# Mako_DSP_Memory_R2_0.net
KiCad netlist of a schematic drawn in Altium Designer
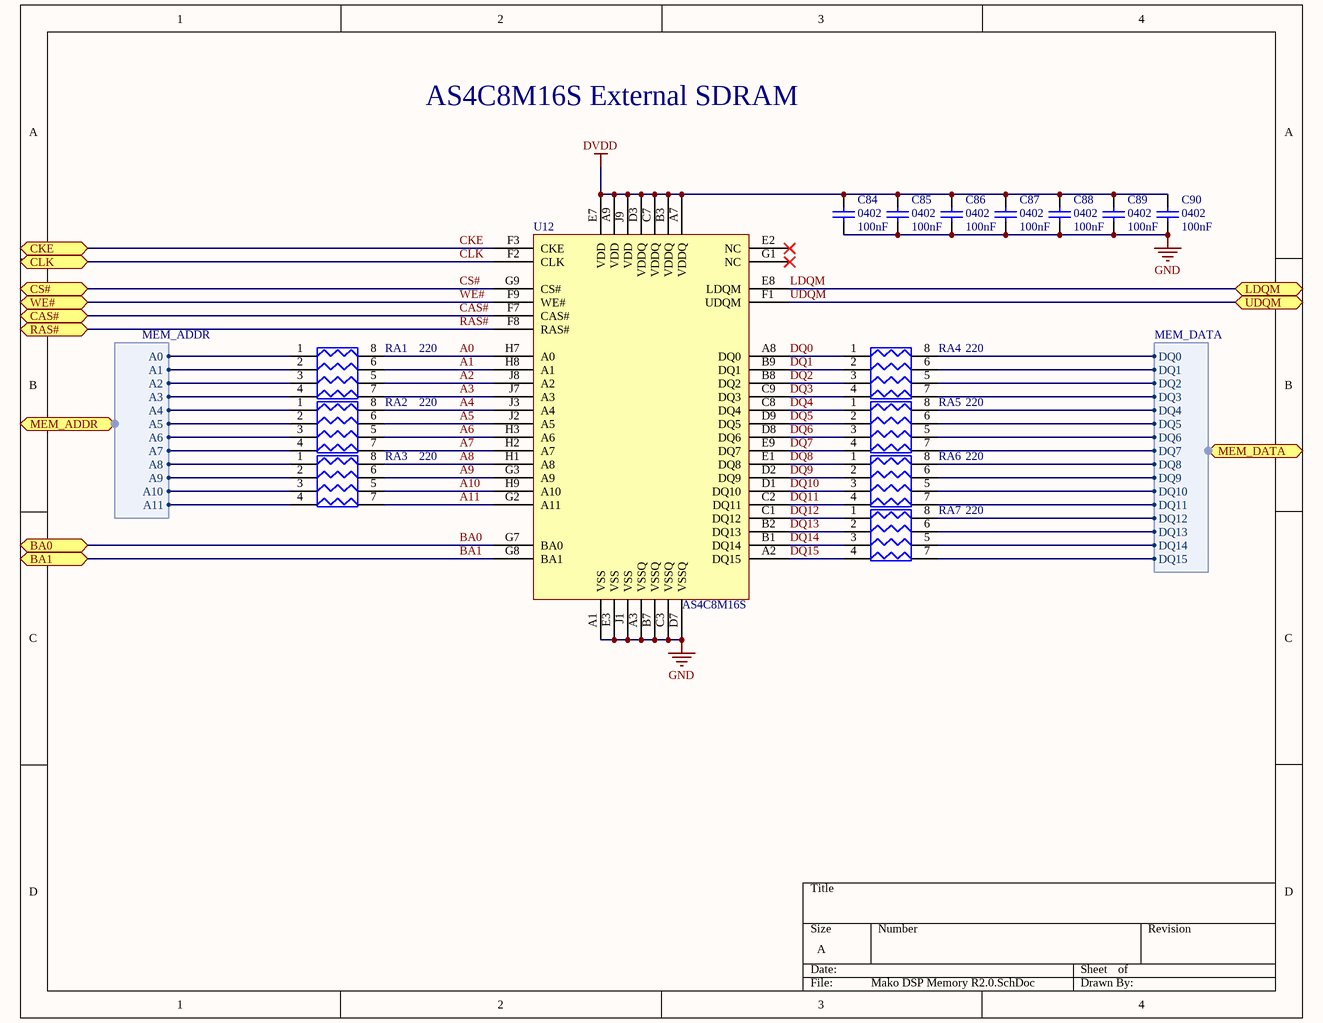
[diagram p0: Mako DSP Memory R2.0.SchDoc]

(export (version "E")
  (design (tool "Eeschema 10.0.6"))
  (components
    (comp (ref "C84")
      (value "0402")
      (footprint "0402")
      (description "Capacitor (Semiconductor SIM Model)")
      (fields (field (name "ALTIUM_VALUE") "100nF") (field (name "PUBLISHER") "Altium Limited"))
      (libsource (lib "Miscellaneous Devices") (part "Cap Semi"))
    )
    (comp (ref "C85")
      (value "0402")
      (footprint "0402")
      (description "Capacitor (Semiconductor SIM Model)")
      (fields (field (name "ALTIUM_VALUE") "100nF") (field (name "PUBLISHER") "Altium Limited"))
      (libsource (lib "Miscellaneous Devices") (part "Cap Semi"))
    )
    (comp (ref "C86")
      (value "0402")
      (footprint "0402")
      (description "Capacitor (Semiconductor SIM Model)")
      (fields (field (name "ALTIUM_VALUE") "100nF") (field (name "PUBLISHER") "Altium Limited"))
      (libsource (lib "Miscellaneous Devices") (part "Cap Semi"))
    )
    (comp (ref "C87")
      (value "0402")
      (footprint "0402")
      (description "Capacitor (Semiconductor SIM Model)")
      (fields (field (name "ALTIUM_VALUE") "100nF") (field (name "PUBLISHER") "Altium Limited"))
      (libsource (lib "Miscellaneous Devices") (part "Cap Semi"))
    )
    (comp (ref "C88")
      (value "0402")
      (footprint "0402")
      (description "Capacitor (Semiconductor SIM Model)")
      (fields (field (name "ALTIUM_VALUE") "100nF") (field (name "PUBLISHER") "Altium Limited"))
      (libsource (lib "Miscellaneous Devices") (part "Cap Semi"))
    )
    (comp (ref "C89")
      (value "0402")
      (footprint "0402")
      (description "Capacitor (Semiconductor SIM Model)")
      (fields (field (name "ALTIUM_VALUE") "100nF") (field (name "PUBLISHER") "Altium Limited"))
      (libsource (lib "Miscellaneous Devices") (part "Cap Semi"))
    )
    (comp (ref "C90")
      (value "0402")
      (footprint "0402")
      (description "Capacitor (Semiconductor SIM Model)")
      (fields (field (name "ALTIUM_VALUE") "100nF") (field (name "PUBLISHER") "Altium Limited"))
      (libsource (lib "Miscellaneous Devices") (part "Cap Semi"))
    )
    (comp (ref "RA1")
      (value "220")
      (footprint "742C083")
      (description "Resistor array")
      (fields (field (name "Comment") "RESISTOR ARRAY"))
      (libsource (lib "Mako DSP Schematic Library") (part "RESISTOR ARRAY"))
    )
    (comp (ref "RA2")
      (value "220")
      (footprint "742C083")
      (description "Resistor array")
      (fields (field (name "Comment") "RESISTOR ARRAY"))
      (libsource (lib "Mako DSP Schematic Library") (part "RESISTOR ARRAY"))
    )
    (comp (ref "RA3")
      (value "220")
      (footprint "742C083")
      (description "Resistor array")
      (fields (field (name "Comment") "RESISTOR ARRAY"))
      (libsource (lib "Mako DSP Schematic Library") (part "RESISTOR ARRAY"))
    )
    (comp (ref "RA4")
      (value "220")
      (footprint "742C083")
      (description "Resistor array")
      (fields (field (name "Comment") "RESISTOR ARRAY"))
      (libsource (lib "Mako DSP Schematic Library") (part "RESISTOR ARRAY"))
    )
    (comp (ref "RA5")
      (value "220")
      (footprint "742C083")
      (description "Resistor array")
      (fields (field (name "Comment") "RESISTOR ARRAY"))
      (libsource (lib "Mako DSP Schematic Library") (part "RESISTOR ARRAY"))
    )
    (comp (ref "RA6")
      (value "220")
      (footprint "742C083")
      (description "Resistor array")
      (fields (field (name "Comment") "RESISTOR ARRAY"))
      (libsource (lib "Mako DSP Schematic Library") (part "RESISTOR ARRAY"))
    )
    (comp (ref "RA7")
      (value "220")
      (footprint "742C083")
      (description "Resistor array")
      (fields (field (name "Comment") "RESISTOR ARRAY"))
      (libsource (lib "Mako DSP Schematic Library") (part "RESISTOR ARRAY"))
    )
    (comp (ref "U12")
      (value "AS4C8M16S")
      (footprint "AS4C8M16S")
      (libsource (lib "Mako DSP Schematic Library") (part "AS4C8M16S"))
    )
  )
  (nets
    (net (code "3") (name "/A0") (class "Default")
      (node (ref "RA1") (pin "8") (pinfunction "8_8") (pintype "passive"))
      (node (ref "U12") (pin "H7") (pinfunction "A0_H7") (pintype "passive"))
    )
    (net (code "4") (name "/A1") (class "Default")
      (node (ref "RA1") (pin "6") (pinfunction "6_6") (pintype "passive"))
      (node (ref "U12") (pin "H8") (pinfunction "A1_H8") (pintype "passive"))
    )
    (net (code "5") (name "/A2") (class "Default")
      (node (ref "RA1") (pin "5") (pinfunction "5_5") (pintype "passive"))
      (node (ref "U12") (pin "J8") (pinfunction "A2_J8") (pintype "passive"))
    )
    (net (code "6") (name "/A3") (class "Default")
      (node (ref "RA1") (pin "7") (pinfunction "7_7") (pintype "passive"))
      (node (ref "U12") (pin "J7") (pinfunction "A3_J7") (pintype "passive"))
    )
    (net (code "7") (name "/A4") (class "Default")
      (node (ref "RA2") (pin "8") (pinfunction "8_8") (pintype "passive"))
      (node (ref "U12") (pin "J3") (pinfunction "A4_J3") (pintype "passive"))
    )
    (net (code "8") (name "/A5") (class "Default")
      (node (ref "RA2") (pin "6") (pinfunction "6_6") (pintype "passive"))
      (node (ref "U12") (pin "J2") (pinfunction "A5_J2") (pintype "passive"))
    )
    (net (code "9") (name "/A6") (class "Default")
      (node (ref "RA2") (pin "5") (pinfunction "5_5") (pintype "passive"))
      (node (ref "U12") (pin "H3") (pinfunction "A6_H3") (pintype "passive"))
    )
    (net (code "10") (name "/A7") (class "Default")
      (node (ref "RA2") (pin "7") (pinfunction "7_7") (pintype "passive"))
      (node (ref "U12") (pin "H2") (pinfunction "A7_H2") (pintype "passive"))
    )
    (net (code "11") (name "/A8") (class "Default")
      (node (ref "RA3") (pin "8") (pinfunction "8_8") (pintype "passive"))
      (node (ref "U12") (pin "H1") (pinfunction "A8_H1") (pintype "passive"))
    )
    (net (code "12") (name "/A9") (class "Default")
      (node (ref "RA3") (pin "6") (pinfunction "6_6") (pintype "passive"))
      (node (ref "U12") (pin "G3") (pinfunction "A9_G3") (pintype "passive"))
    )
    (net (code "13") (name "/A10") (class "Default")
      (node (ref "RA3") (pin "5") (pinfunction "5_5") (pintype "passive"))
      (node (ref "U12") (pin "H9") (pinfunction "A10_H9") (pintype "passive"))
    )
    (net (code "14") (name "/A11") (class "Default")
      (node (ref "RA3") (pin "7") (pinfunction "7_7") (pintype "passive"))
      (node (ref "U12") (pin "G2") (pinfunction "A11_G2") (pintype "passive"))
    )
    (net (code "15") (name "/BA0") (class "Default")
      (node (ref "U12") (pin "G7") (pinfunction "BA0_G7") (pintype "passive"))
    )
    (net (code "16") (name "/BA1") (class "Default")
      (node (ref "U12") (pin "G8") (pinfunction "BA1_G8") (pintype "passive"))
    )
    (net (code "17") (name "/CAS#") (class "Default")
      (node (ref "U12") (pin "F7") (pinfunction "CAS#_F7") (pintype "passive"))
    )
    (net (code "18") (name "/CKE") (class "Default")
      (node (ref "U12") (pin "F3") (pinfunction "CKE_F3") (pintype "passive"))
    )
    (net (code "19") (name "/CLK") (class "Default")
      (node (ref "U12") (pin "F2") (pinfunction "CLK_F2") (pintype "passive"))
    )
    (net (code "20") (name "/CS#") (class "Default")
      (node (ref "U12") (pin "G9") (pinfunction "CS#_G9") (pintype "passive"))
    )
    (net (code "21") (name "/DQ0") (class "Default")
      (node (ref "RA4") (pin "1") (pinfunction "1_1") (pintype "passive"))
      (node (ref "U12") (pin "A8") (pinfunction "DQ0_A8") (pintype "passive"))
    )
    (net (code "22") (name "/DQ1") (class "Default")
      (node (ref "RA4") (pin "2") (pinfunction "2_2") (pintype "passive"))
      (node (ref "U12") (pin "B9") (pinfunction "DQ1_B9") (pintype "passive"))
    )
    (net (code "23") (name "/DQ2") (class "Default")
      (node (ref "RA4") (pin "3") (pinfunction "3_3") (pintype "passive"))
      (node (ref "U12") (pin "B8") (pinfunction "DQ2_B8") (pintype "passive"))
    )
    (net (code "24") (name "/DQ3") (class "Default")
      (node (ref "RA4") (pin "4") (pinfunction "4_4") (pintype "passive"))
      (node (ref "U12") (pin "C9") (pinfunction "DQ3_C9") (pintype "passive"))
    )
    (net (code "25") (name "/DQ4") (class "Default")
      (node (ref "RA5") (pin "1") (pinfunction "1_1") (pintype "passive"))
      (node (ref "U12") (pin "C8") (pinfunction "DQ4_C8") (pintype "passive"))
    )
    (net (code "26") (name "/DQ5") (class "Default")
      (node (ref "RA5") (pin "2") (pinfunction "2_2") (pintype "passive"))
      (node (ref "U12") (pin "D9") (pinfunction "DQ5_D9") (pintype "passive"))
    )
    (net (code "27") (name "/DQ6") (class "Default")
      (node (ref "RA5") (pin "3") (pinfunction "3_3") (pintype "passive"))
      (node (ref "U12") (pin "D8") (pinfunction "DQ6_D8") (pintype "passive"))
    )
    (net (code "28") (name "/DQ7") (class "Default")
      (node (ref "RA5") (pin "4") (pinfunction "4_4") (pintype "passive"))
      (node (ref "U12") (pin "E9") (pinfunction "DQ7_E9") (pintype "passive"))
    )
    (net (code "29") (name "/DQ8") (class "Default")
      (node (ref "RA6") (pin "1") (pinfunction "1_1") (pintype "passive"))
      (node (ref "U12") (pin "E1") (pinfunction "DQ8_E1") (pintype "passive"))
    )
    (net (code "30") (name "/DQ9") (class "Default")
      (node (ref "RA6") (pin "2") (pinfunction "2_2") (pintype "passive"))
      (node (ref "U12") (pin "D2") (pinfunction "DQ9_D2") (pintype "passive"))
    )
    (net (code "31") (name "/DQ10") (class "Default")
      (node (ref "RA6") (pin "3") (pinfunction "3_3") (pintype "passive"))
      (node (ref "U12") (pin "D1") (pinfunction "DQ10_D1") (pintype "passive"))
    )
    (net (code "32") (name "/DQ11") (class "Default")
      (node (ref "RA6") (pin "4") (pinfunction "4_4") (pintype "passive"))
      (node (ref "U12") (pin "C2") (pinfunction "DQ11_C2") (pintype "passive"))
    )
    (net (code "33") (name "/DQ12") (class "Default")
      (node (ref "RA7") (pin "1") (pinfunction "1_1") (pintype "passive"))
      (node (ref "U12") (pin "C1") (pinfunction "DQ12_C1") (pintype "passive"))
    )
    (net (code "34") (name "/DQ13") (class "Default")
      (node (ref "RA7") (pin "2") (pinfunction "2_2") (pintype "passive"))
      (node (ref "U12") (pin "B2") (pinfunction "DQ13_B2") (pintype "passive"))
    )
    (net (code "35") (name "/DQ14") (class "Default")
      (node (ref "RA7") (pin "3") (pinfunction "3_3") (pintype "passive"))
      (node (ref "U12") (pin "B1") (pinfunction "DQ14_B1") (pintype "passive"))
    )
    (net (code "36") (name "/DQ15") (class "Default")
      (node (ref "RA7") (pin "4") (pinfunction "4_4") (pintype "passive"))
      (node (ref "U12") (pin "A2") (pinfunction "DQ15_A2") (pintype "passive"))
    )
    (net (code "37") (name "/LDQM") (class "Default")
      (node (ref "U12") (pin "E8") (pinfunction "LDQM_E8") (pintype "passive"))
    )
    (net (code "38") (name "/RAS#") (class "Default")
      (node (ref "U12") (pin "F8") (pinfunction "RAS#_F8") (pintype "passive"))
    )
    (net (code "39") (name "/UDQM") (class "Default")
      (node (ref "U12") (pin "F1") (pinfunction "UDQM_F1") (pintype "passive"))
    )
    (net (code "40") (name "/WE#") (class "Default")
      (node (ref "U12") (pin "F9") (pinfunction "WE#_F9") (pintype "passive"))
    )
    (net (code "43") (name "DVDD") (class "Default")
      (node (ref "C84") (pin "2") (pinfunction "2_2") (pintype "passive"))
      (node (ref "C85") (pin "2") (pinfunction "2_2") (pintype "passive"))
      (node (ref "C86") (pin "2") (pinfunction "2_2") (pintype "passive"))
      (node (ref "C87") (pin "2") (pinfunction "2_2") (pintype "passive"))
      (node (ref "C88") (pin "2") (pinfunction "2_2") (pintype "passive"))
      (node (ref "C89") (pin "2") (pinfunction "2_2") (pintype "passive"))
      (node (ref "C90") (pin "2") (pinfunction "2_2") (pintype "passive"))
      (node (ref "U12") (pin "A7") (pinfunction "VDDQ_A7") (pintype "passive"))
      (node (ref "U12") (pin "A9") (pinfunction "VDD_A9") (pintype "passive"))
      (node (ref "U12") (pin "B3") (pinfunction "VDDQ_B3") (pintype "passive"))
      (node (ref "U12") (pin "C7") (pinfunction "VDDQ_C7") (pintype "passive"))
      (node (ref "U12") (pin "D3") (pinfunction "VDDQ_D3") (pintype "passive"))
      (node (ref "U12") (pin "E7") (pinfunction "VDD_E7") (pintype "passive"))
      (node (ref "U12") (pin "J9") (pinfunction "VDD_J9") (pintype "passive"))
    )
    (net (code "44") (name "GND") (class "Default")
      (node (ref "C84") (pin "1") (pinfunction "1_1") (pintype "passive"))
      (node (ref "C85") (pin "1") (pinfunction "1_1") (pintype "passive"))
      (node (ref "C86") (pin "1") (pinfunction "1_1") (pintype "passive"))
      (node (ref "C87") (pin "1") (pinfunction "1_1") (pintype "passive"))
      (node (ref "C88") (pin "1") (pinfunction "1_1") (pintype "passive"))
      (node (ref "C89") (pin "1") (pinfunction "1_1") (pintype "passive"))
      (node (ref "C90") (pin "1") (pinfunction "1_1") (pintype "passive"))
      (node (ref "U12") (pin "A1") (pinfunction "VSS_A1") (pintype "passive"))
      (node (ref "U12") (pin "A3") (pinfunction "VSSQ_A3") (pintype "passive"))
      (node (ref "U12") (pin "B7") (pinfunction "VSSQ_B7") (pintype "passive"))
      (node (ref "U12") (pin "C3") (pinfunction "VSSQ_C3") (pintype "passive"))
      (node (ref "U12") (pin "D7") (pinfunction "VSSQ_D7") (pintype "passive"))
      (node (ref "U12") (pin "E3") (pinfunction "VSS_E3") (pintype "passive"))
      (node (ref "U12") (pin "J1") (pinfunction "VSS_J1") (pintype "passive"))
    )
    (net (code "45") (name "unconnected-(RA1-Pad1)") (class "Default")
      (node (ref "RA1") (pin "1") (pinfunction "1_1") (pintype "passive"))
    )
    (net (code "46") (name "unconnected-(RA1-Pad2)") (class "Default")
      (node (ref "RA1") (pin "2") (pinfunction "2_2") (pintype "passive"))
    )
    (net (code "47") (name "unconnected-(RA1-Pad3)") (class "Default")
      (node (ref "RA1") (pin "3") (pinfunction "3_3") (pintype "passive"))
    )
    (net (code "48") (name "unconnected-(RA1-Pad4)") (class "Default")
      (node (ref "RA1") (pin "4") (pinfunction "4_4") (pintype "passive"))
    )
    (net (code "49") (name "unconnected-(RA2-Pad1)") (class "Default")
      (node (ref "RA2") (pin "1") (pinfunction "1_1") (pintype "passive"))
    )
    (net (code "50") (name "unconnected-(RA2-Pad2)") (class "Default")
      (node (ref "RA2") (pin "2") (pinfunction "2_2") (pintype "passive"))
    )
    (net (code "51") (name "unconnected-(RA2-Pad3)") (class "Default")
      (node (ref "RA2") (pin "3") (pinfunction "3_3") (pintype "passive"))
    )
    (net (code "52") (name "unconnected-(RA2-Pad4)") (class "Default")
      (node (ref "RA2") (pin "4") (pinfunction "4_4") (pintype "passive"))
    )
    (net (code "53") (name "unconnected-(RA3-Pad1)") (class "Default")
      (node (ref "RA3") (pin "1") (pinfunction "1_1") (pintype "passive"))
    )
    (net (code "54") (name "unconnected-(RA3-Pad2)") (class "Default")
      (node (ref "RA3") (pin "2") (pinfunction "2_2") (pintype "passive"))
    )
    (net (code "55") (name "unconnected-(RA3-Pad3)") (class "Default")
      (node (ref "RA3") (pin "3") (pinfunction "3_3") (pintype "passive"))
    )
    (net (code "56") (name "unconnected-(RA3-Pad4)") (class "Default")
      (node (ref "RA3") (pin "4") (pinfunction "4_4") (pintype "passive"))
    )
    (net (code "57") (name "unconnected-(RA4-Pad5)") (class "Default")
      (node (ref "RA4") (pin "5") (pinfunction "5_5") (pintype "passive"))
    )
    (net (code "58") (name "unconnected-(RA4-Pad6)") (class "Default")
      (node (ref "RA4") (pin "6") (pinfunction "6_6") (pintype "passive"))
    )
    (net (code "59") (name "unconnected-(RA4-Pad7)") (class "Default")
      (node (ref "RA4") (pin "7") (pinfunction "7_7") (pintype "passive"))
    )
    (net (code "60") (name "unconnected-(RA4-Pad8)") (class "Default")
      (node (ref "RA4") (pin "8") (pinfunction "8_8") (pintype "passive"))
    )
    (net (code "61") (name "unconnected-(RA5-Pad5)") (class "Default")
      (node (ref "RA5") (pin "5") (pinfunction "5_5") (pintype "passive"))
    )
    (net (code "62") (name "unconnected-(RA5-Pad6)") (class "Default")
      (node (ref "RA5") (pin "6") (pinfunction "6_6") (pintype "passive"))
    )
    (net (code "63") (name "unconnected-(RA5-Pad7)") (class "Default")
      (node (ref "RA5") (pin "7") (pinfunction "7_7") (pintype "passive"))
    )
    (net (code "64") (name "unconnected-(RA5-Pad8)") (class "Default")
      (node (ref "RA5") (pin "8") (pinfunction "8_8") (pintype "passive"))
    )
    (net (code "65") (name "unconnected-(RA6-Pad5)") (class "Default")
      (node (ref "RA6") (pin "5") (pinfunction "5_5") (pintype "passive"))
    )
    (net (code "66") (name "unconnected-(RA6-Pad6)") (class "Default")
      (node (ref "RA6") (pin "6") (pinfunction "6_6") (pintype "passive"))
    )
    (net (code "67") (name "unconnected-(RA6-Pad7)") (class "Default")
      (node (ref "RA6") (pin "7") (pinfunction "7_7") (pintype "passive"))
    )
    (net (code "68") (name "unconnected-(RA6-Pad8)") (class "Default")
      (node (ref "RA6") (pin "8") (pinfunction "8_8") (pintype "passive"))
    )
    (net (code "69") (name "unconnected-(RA7-Pad5)") (class "Default")
      (node (ref "RA7") (pin "5") (pinfunction "5_5") (pintype "passive"))
    )
    (net (code "70") (name "unconnected-(RA7-Pad6)") (class "Default")
      (node (ref "RA7") (pin "6") (pinfunction "6_6") (pintype "passive"))
    )
    (net (code "71") (name "unconnected-(RA7-Pad7)") (class "Default")
      (node (ref "RA7") (pin "7") (pinfunction "7_7") (pintype "passive"))
    )
    (net (code "72") (name "unconnected-(RA7-Pad8)") (class "Default")
      (node (ref "RA7") (pin "8") (pinfunction "8_8") (pintype "passive"))
    )
    (net (code "73") (name "unconnected-(U12-NC-PadE2)") (class "Default")
      (node (ref "U12") (pin "E2") (pinfunction "NC_E2") (pintype "passive+no_connect"))
    )
    (net (code "74") (name "unconnected-(U12-NC-PadG1)") (class "Default")
      (node (ref "U12") (pin "G1") (pinfunction "NC_G1") (pintype "passive+no_connect"))
    )
  )
)
